# LPDDR4.net
KiCad netlist of a schematic drawn in Altium Designer
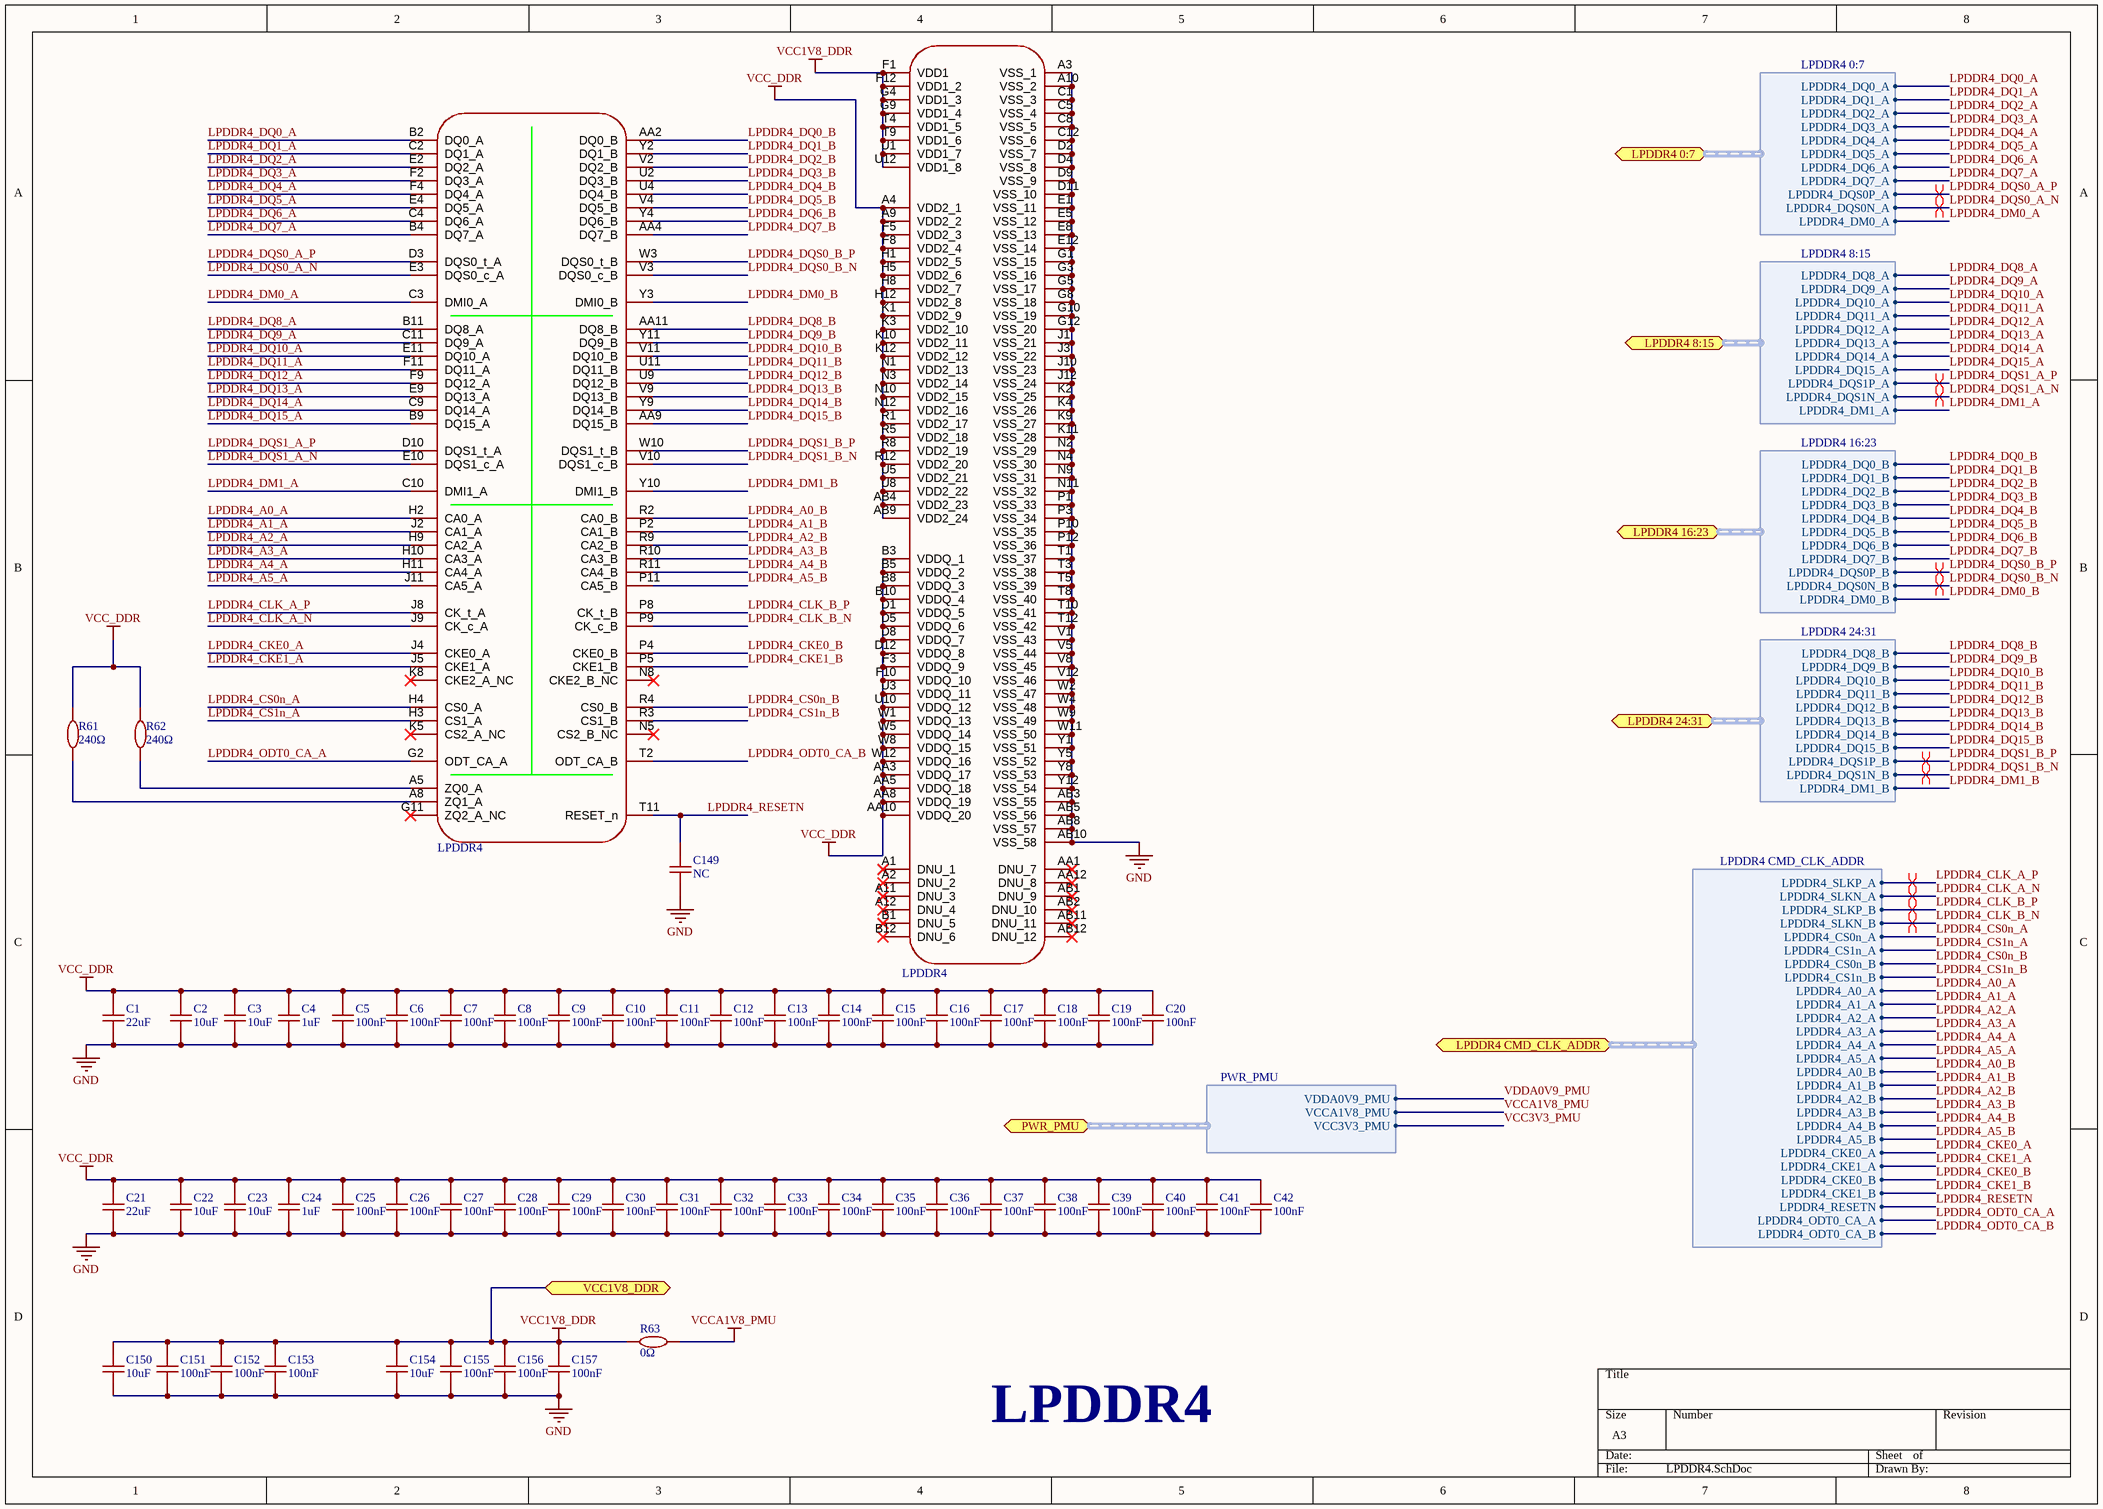
[diagram p0: LPDDR4.SchDoc]

(export (version "E")
  (design (tool "Eeschema 10.0.6"))
  (components
    (comp (ref "C1")
      (value "22uF")
      (footprint "C0603")
      (description "16V 22uF X5R ±20% 0603 Ceramic Capacitors ROHS")
      (libsource (lib "RLC") (part "22uF"))
    )
    (comp (ref "C2")
      (value "10uF")
      (footprint "C0603")
      (description "10V 10uF X5R ±10% 0603 Ceramic Capacitors ROHS")
      (libsource (lib "RLC") (part "10uF"))
    )
    (comp (ref "C3")
      (value "10uF")
      (footprint "C0603")
      (description "10V 10uF X5R ±10% 0603 Ceramic Capacitors ROHS")
      (libsource (lib "RLC") (part "10uF"))
    )
    (comp (ref "C4")
      (value "1uF")
      (footprint "C0402")
      (description "50V 1uF X5R ±10% 0402 Ceramic Capacitors ROHS")
      (libsource (lib "RLC") (part "1uF"))
    )
    (comp (ref "C5")
      (value "100nF")
      (footprint "C0402")
      (description "50V 100nF X7R ±10% 0402 Ceramic Capacitors ROHS")
      (libsource (lib "RLC") (part "100nF"))
    )
    (comp (ref "C6")
      (value "100nF")
      (footprint "C0402")
      (description "50V 100nF X7R ±10% 0402 Ceramic Capacitors ROHS")
      (libsource (lib "RLC") (part "100nF"))
    )
    (comp (ref "C7")
      (value "100nF")
      (footprint "C0402")
      (description "50V 100nF X7R ±10% 0402 Ceramic Capacitors ROHS")
      (libsource (lib "RLC") (part "100nF"))
    )
    (comp (ref "C8")
      (value "100nF")
      (footprint "C0402")
      (description "50V 100nF X7R ±10% 0402 Ceramic Capacitors ROHS")
      (libsource (lib "RLC") (part "100nF"))
    )
    (comp (ref "C9")
      (value "100nF")
      (footprint "C0402")
      (description "50V 100nF X7R ±10% 0402 Ceramic Capacitors ROHS")
      (libsource (lib "RLC") (part "100nF"))
    )
    (comp (ref "C10")
      (value "100nF")
      (footprint "C0402")
      (description "50V 100nF X7R ±10% 0402 Ceramic Capacitors ROHS")
      (libsource (lib "RLC") (part "100nF"))
    )
    (comp (ref "C11")
      (value "100nF")
      (footprint "C0402")
      (description "50V 100nF X7R ±10% 0402 Ceramic Capacitors ROHS")
      (libsource (lib "RLC") (part "100nF"))
    )
    (comp (ref "C12")
      (value "100nF")
      (footprint "C0402")
      (description "50V 100nF X7R ±10% 0402 Ceramic Capacitors ROHS")
      (libsource (lib "RLC") (part "100nF"))
    )
    (comp (ref "C13")
      (value "100nF")
      (footprint "C0402")
      (description "50V 100nF X7R ±10% 0402 Ceramic Capacitors ROHS")
      (libsource (lib "RLC") (part "100nF"))
    )
    (comp (ref "C14")
      (value "100nF")
      (footprint "C0402")
      (description "50V 100nF X7R ±10% 0402 Ceramic Capacitors ROHS")
      (libsource (lib "RLC") (part "100nF"))
    )
    (comp (ref "C15")
      (value "100nF")
      (footprint "C0402")
      (description "50V 100nF X7R ±10% 0402 Ceramic Capacitors ROHS")
      (libsource (lib "RLC") (part "100nF"))
    )
    (comp (ref "C16")
      (value "100nF")
      (footprint "C0402")
      (description "50V 100nF X7R ±10% 0402 Ceramic Capacitors ROHS")
      (libsource (lib "RLC") (part "100nF"))
    )
    (comp (ref "C17")
      (value "100nF")
      (footprint "C0402")
      (description "50V 100nF X7R ±10% 0402 Ceramic Capacitors ROHS")
      (libsource (lib "RLC") (part "100nF"))
    )
    (comp (ref "C18")
      (value "100nF")
      (footprint "C0402")
      (description "50V 100nF X7R ±10% 0402 Ceramic Capacitors ROHS")
      (libsource (lib "RLC") (part "100nF"))
    )
    (comp (ref "C19")
      (value "100nF")
      (footprint "C0402")
      (description "50V 100nF X7R ±10% 0402 Ceramic Capacitors ROHS")
      (libsource (lib "RLC") (part "100nF"))
    )
    (comp (ref "C20")
      (value "100nF")
      (footprint "C0402")
      (description "50V 100nF X7R ±10% 0402 Ceramic Capacitors ROHS")
      (libsource (lib "RLC") (part "100nF"))
    )
    (comp (ref "C21")
      (value "22uF")
      (footprint "C0603")
      (description "16V 22uF X5R ±20% 0603 Ceramic Capacitors ROHS")
      (libsource (lib "RLC") (part "22uF"))
    )
    (comp (ref "C22")
      (value "10uF")
      (footprint "C0603")
      (description "10V 10uF X5R ±10% 0603 Ceramic Capacitors ROHS")
      (libsource (lib "RLC") (part "10uF"))
    )
    (comp (ref "C23")
      (value "10uF")
      (footprint "C0603")
      (description "10V 10uF X5R ±10% 0603 Ceramic Capacitors ROHS")
      (libsource (lib "RLC") (part "10uF"))
    )
    (comp (ref "C24")
      (value "1uF")
      (footprint "C0402")
      (description "50V 1uF X5R ±10% 0402 Ceramic Capacitors ROHS")
      (libsource (lib "RLC") (part "1uF"))
    )
    (comp (ref "C25")
      (value "100nF")
      (footprint "C0402")
      (description "50V 100nF X7R ±10% 0402 Ceramic Capacitors ROHS")
      (libsource (lib "RLC") (part "100nF"))
    )
    (comp (ref "C26")
      (value "100nF")
      (footprint "C0402")
      (description "50V 100nF X7R ±10% 0402 Ceramic Capacitors ROHS")
      (libsource (lib "RLC") (part "100nF"))
    )
    (comp (ref "C27")
      (value "100nF")
      (footprint "C0402")
      (description "50V 100nF X7R ±10% 0402 Ceramic Capacitors ROHS")
      (libsource (lib "RLC") (part "100nF"))
    )
    (comp (ref "C28")
      (value "100nF")
      (footprint "C0402")
      (description "50V 100nF X7R ±10% 0402 Ceramic Capacitors ROHS")
      (libsource (lib "RLC") (part "100nF"))
    )
    (comp (ref "C29")
      (value "100nF")
      (footprint "C0402")
      (description "50V 100nF X7R ±10% 0402 Ceramic Capacitors ROHS")
      (libsource (lib "RLC") (part "100nF"))
    )
    (comp (ref "C30")
      (value "100nF")
      (footprint "C0402")
      (description "50V 100nF X7R ±10% 0402 Ceramic Capacitors ROHS")
      (libsource (lib "RLC") (part "100nF"))
    )
    (comp (ref "C31")
      (value "100nF")
      (footprint "C0402")
      (description "50V 100nF X7R ±10% 0402 Ceramic Capacitors ROHS")
      (libsource (lib "RLC") (part "100nF"))
    )
    (comp (ref "C32")
      (value "100nF")
      (footprint "C0402")
      (description "50V 100nF X7R ±10% 0402 Ceramic Capacitors ROHS")
      (libsource (lib "RLC") (part "100nF"))
    )
    (comp (ref "C33")
      (value "100nF")
      (footprint "C0402")
      (description "50V 100nF X7R ±10% 0402 Ceramic Capacitors ROHS")
      (libsource (lib "RLC") (part "100nF"))
    )
    (comp (ref "C34")
      (value "100nF")
      (footprint "C0402")
      (description "50V 100nF X7R ±10% 0402 Ceramic Capacitors ROHS")
      (libsource (lib "RLC") (part "100nF"))
    )
    (comp (ref "C35")
      (value "100nF")
      (footprint "C0402")
      (description "50V 100nF X7R ±10% 0402 Ceramic Capacitors ROHS")
      (libsource (lib "RLC") (part "100nF"))
    )
    (comp (ref "C36")
      (value "100nF")
      (footprint "C0402")
      (description "50V 100nF X7R ±10% 0402 Ceramic Capacitors ROHS")
      (libsource (lib "RLC") (part "100nF"))
    )
    (comp (ref "C37")
      (value "100nF")
      (footprint "C0402")
      (description "50V 100nF X7R ±10% 0402 Ceramic Capacitors ROHS")
      (libsource (lib "RLC") (part "100nF"))
    )
    (comp (ref "C38")
      (value "100nF")
      (footprint "C0402")
      (description "50V 100nF X7R ±10% 0402 Ceramic Capacitors ROHS")
      (libsource (lib "RLC") (part "100nF"))
    )
    (comp (ref "C39")
      (value "100nF")
      (footprint "C0402")
      (description "50V 100nF X7R ±10% 0402 Ceramic Capacitors ROHS")
      (libsource (lib "RLC") (part "100nF"))
    )
    (comp (ref "C40")
      (value "100nF")
      (footprint "C0402")
      (description "50V 100nF X7R ±10% 0402 Ceramic Capacitors ROHS")
      (libsource (lib "RLC") (part "100nF"))
    )
    (comp (ref "C41")
      (value "100nF")
      (footprint "C0402")
      (description "50V 100nF X7R ±10% 0402 Ceramic Capacitors ROHS")
      (libsource (lib "RLC") (part "100nF"))
    )
    (comp (ref "C42")
      (value "100nF")
      (footprint "C0402")
      (description "50V 100nF X7R ±10% 0402 Ceramic Capacitors ROHS")
      (libsource (lib "RLC") (part "100nF"))
    )
    (comp (ref "C149")
      (value "NC")
      (footprint "C0402")
      (description "50V 10nF X7R ±10% 0402 Ceramic Capacitors ROHS")
      (libsource (lib "RLC") (part "10nF"))
    )
    (comp (ref "C150")
      (value "10uF")
      (footprint "C0603")
      (description "10V 10uF X5R ±10% 0603 Ceramic Capacitors ROHS")
      (libsource (lib "RLC") (part "10uF"))
    )
    (comp (ref "C151")
      (value "100nF")
      (footprint "C0402")
      (description "50V 100nF X7R ±10% 0402 Ceramic Capacitors ROHS")
      (libsource (lib "RLC") (part "100nF"))
    )
    (comp (ref "C152")
      (value "100nF")
      (footprint "C0402")
      (description "50V 100nF X7R ±10% 0402 Ceramic Capacitors ROHS")
      (libsource (lib "RLC") (part "100nF"))
    )
    (comp (ref "C153")
      (value "100nF")
      (footprint "C0402")
      (description "50V 100nF X7R ±10% 0402 Ceramic Capacitors ROHS")
      (libsource (lib "RLC") (part "100nF"))
    )
    (comp (ref "C154")
      (value "10uF")
      (footprint "C0603")
      (description "10V 10uF X5R ±10% 0603 Ceramic Capacitors ROHS")
      (libsource (lib "RLC") (part "10uF"))
    )
    (comp (ref "C155")
      (value "100nF")
      (footprint "C0402")
      (description "50V 100nF X7R ±10% 0402 Ceramic Capacitors ROHS")
      (libsource (lib "RLC") (part "100nF"))
    )
    (comp (ref "C156")
      (value "100nF")
      (footprint "C0402")
      (description "50V 100nF X7R ±10% 0402 Ceramic Capacitors ROHS")
      (libsource (lib "RLC") (part "100nF"))
    )
    (comp (ref "C157")
      (value "100nF")
      (footprint "C0402")
      (description "50V 100nF X7R ±10% 0402 Ceramic Capacitors ROHS")
      (libsource (lib "RLC") (part "100nF"))
    )
    (comp (ref "R61")
      (value "240Ω")
      (footprint "R0402")
      (description "240Ω 62.5mW 50V ±100ppm/℃ Thick Film Resistor ±1% 0402 Chip Resistor - Surface Mount ROHS")
      (libsource (lib "RLC") (part "240Ω"))
    )
    (comp (ref "R62")
      (value "240Ω")
      (footprint "R0402")
      (description "240Ω 62.5mW 50V ±100ppm/℃ Thick Film Resistor ±1% 0402 Chip Resistor - Surface Mount ROHS")
      (libsource (lib "RLC") (part "240Ω"))
    )
    (comp (ref "R63")
      (value "0Ω")
      (footprint "R0402")
      (description "0Ω 62.5mW 50V Thick Film Resistor ±1% 0402 Chip Resistor - Surface Mount ROHS")
      (libsource (lib "RLC") (part "0Ω"))
    )
    (comp (ref "U1")
      (value "LPDDR4")
      (footprint "FBGA-200_L15.0-W10.0-BL_H9HCNNNBKUMLXR")
      (description "LPDDR4 - SDRAM是一种高速同步DRAM器件，内部配置有1个或2个通道。单通道由8个存储体组成，每通道密度为1 Gb至16 Gb。双通道由8个存储体组成，每通道密度为2 Gb至32 Gb")
      (libsource (lib "IC") (part "LPDDR4"))
    )
  )
  (nets
    (net (code "8") (name "/LPDDR4_A0_A") (class "Default")
      (node (ref "U1") (pin "H2") (pinfunction "CA0_A_H2") (pintype "passive"))
    )
    (net (code "9") (name "/LPDDR4_A0_B") (class "Default")
      (node (ref "U1") (pin "R2") (pinfunction "CA0_B_R2") (pintype "passive"))
    )
    (net (code "10") (name "/LPDDR4_A1_A") (class "Default")
      (node (ref "U1") (pin "J2") (pinfunction "CA1_A_J2") (pintype "passive"))
    )
    (net (code "11") (name "/LPDDR4_A1_B") (class "Default")
      (node (ref "U1") (pin "P2") (pinfunction "CA1_B_P2") (pintype "passive"))
    )
    (net (code "12") (name "/LPDDR4_A2_A") (class "Default")
      (node (ref "U1") (pin "H9") (pinfunction "CA2_A_H9") (pintype "passive"))
    )
    (net (code "13") (name "/LPDDR4_A2_B") (class "Default")
      (node (ref "U1") (pin "R9") (pinfunction "CA2_B_R9") (pintype "passive"))
    )
    (net (code "14") (name "/LPDDR4_A3_A") (class "Default")
      (node (ref "U1") (pin "H10") (pinfunction "CA3_A_H10") (pintype "passive"))
    )
    (net (code "15") (name "/LPDDR4_A3_B") (class "Default")
      (node (ref "U1") (pin "R10") (pinfunction "CA3_B_R10") (pintype "passive"))
    )
    (net (code "16") (name "/LPDDR4_A4_A") (class "Default")
      (node (ref "U1") (pin "H11") (pinfunction "CA4_A_H11") (pintype "passive"))
    )
    (net (code "17") (name "/LPDDR4_A4_B") (class "Default")
      (node (ref "U1") (pin "R11") (pinfunction "CA4_B_R11") (pintype "passive"))
    )
    (net (code "18") (name "/LPDDR4_A5_A") (class "Default")
      (node (ref "U1") (pin "J11") (pinfunction "CA5_A_J11") (pintype "passive"))
    )
    (net (code "19") (name "/LPDDR4_A5_B") (class "Default")
      (node (ref "U1") (pin "P11") (pinfunction "CA5_B_P11") (pintype "passive"))
    )
    (net (code "20") (name "/LPDDR4_CKE0_A") (class "Default")
      (node (ref "U1") (pin "J4") (pinfunction "CKE0_A_J4") (pintype "passive"))
    )
    (net (code "21") (name "/LPDDR4_CKE0_B") (class "Default")
      (node (ref "U1") (pin "P4") (pinfunction "CKE0_B_P4") (pintype "passive"))
    )
    (net (code "22") (name "/LPDDR4_CKE1_A") (class "Default")
      (node (ref "U1") (pin "J5") (pinfunction "CKE1_A_J5") (pintype "passive"))
    )
    (net (code "23") (name "/LPDDR4_CKE1_B") (class "Default")
      (node (ref "U1") (pin "P5") (pinfunction "CKE1_B_P5") (pintype "passive"))
    )
    (net (code "24") (name "/LPDDR4_CLK_A_N") (class "Default")
      (node (ref "U1") (pin "J9") (pinfunction "CK_c_A_J9") (pintype "passive"))
    )
    (net (code "25") (name "/LPDDR4_CLK_A_P") (class "Default")
      (node (ref "U1") (pin "J8") (pinfunction "CK_t_A_J8") (pintype "passive"))
    )
    (net (code "26") (name "/LPDDR4_CLK_B_N") (class "Default")
      (node (ref "U1") (pin "P9") (pinfunction "CK_c_B_P9") (pintype "passive"))
    )
    (net (code "27") (name "/LPDDR4_CLK_B_P") (class "Default")
      (node (ref "U1") (pin "P8") (pinfunction "CK_t_B_P8") (pintype "passive"))
    )
    (net (code "28") (name "/LPDDR4_CS0n_A") (class "Default")
      (node (ref "U1") (pin "H4") (pinfunction "CS0_A_H4") (pintype "passive"))
    )
    (net (code "29") (name "/LPDDR4_CS0n_B") (class "Default")
      (node (ref "U1") (pin "R4") (pinfunction "CS0_B_R4") (pintype "passive"))
    )
    (net (code "30") (name "/LPDDR4_CS1n_A") (class "Default")
      (node (ref "U1") (pin "H3") (pinfunction "CS1_A_H3") (pintype "passive"))
    )
    (net (code "31") (name "/LPDDR4_CS1n_B") (class "Default")
      (node (ref "U1") (pin "R3") (pinfunction "CS1_B_R3") (pintype "passive"))
    )
    (net (code "32") (name "/LPDDR4_DM0_A") (class "Default")
      (node (ref "U1") (pin "C3") (pinfunction "DMI0_A_C3") (pintype "passive"))
    )
    (net (code "33") (name "/LPDDR4_DM0_B") (class "Default")
      (node (ref "U1") (pin "Y3") (pinfunction "DMI0_B_Y3") (pintype "passive"))
    )
    (net (code "34") (name "/LPDDR4_DM1_A") (class "Default")
      (node (ref "U1") (pin "C10") (pinfunction "DMI1_A_C10") (pintype "passive"))
    )
    (net (code "35") (name "/LPDDR4_DM1_B") (class "Default")
      (node (ref "U1") (pin "Y10") (pinfunction "DMI1_B_Y10") (pintype "passive"))
    )
    (net (code "36") (name "/LPDDR4_DQ0_A") (class "Default")
      (node (ref "U1") (pin "B2") (pinfunction "DQ0_A_B2") (pintype "passive"))
    )
    (net (code "37") (name "/LPDDR4_DQ0_B") (class "Default")
      (node (ref "U1") (pin "AA2") (pinfunction "DQ0_B_AA2") (pintype "passive"))
    )
    (net (code "38") (name "/LPDDR4_DQ1_A") (class "Default")
      (node (ref "U1") (pin "C2") (pinfunction "DQ1_A_C2") (pintype "passive"))
    )
    (net (code "39") (name "/LPDDR4_DQ1_B") (class "Default")
      (node (ref "U1") (pin "Y2") (pinfunction "DQ1_B_Y2") (pintype "passive"))
    )
    (net (code "40") (name "/LPDDR4_DQ2_A") (class "Default")
      (node (ref "U1") (pin "E2") (pinfunction "DQ2_A_E2") (pintype "passive"))
    )
    (net (code "41") (name "/LPDDR4_DQ2_B") (class "Default")
      (node (ref "U1") (pin "V2") (pinfunction "DQ2_B_V2") (pintype "passive"))
    )
    (net (code "42") (name "/LPDDR4_DQ3_A") (class "Default")
      (node (ref "U1") (pin "F2") (pinfunction "DQ3_A_F2") (pintype "passive"))
    )
    (net (code "43") (name "/LPDDR4_DQ3_B") (class "Default")
      (node (ref "U1") (pin "U2") (pinfunction "DQ3_B_U2") (pintype "passive"))
    )
    (net (code "44") (name "/LPDDR4_DQ4_A") (class "Default")
      (node (ref "U1") (pin "F4") (pinfunction "DQ4_A_F4") (pintype "passive"))
    )
    (net (code "45") (name "/LPDDR4_DQ4_B") (class "Default")
      (node (ref "U1") (pin "U4") (pinfunction "DQ4_B_U4") (pintype "passive"))
    )
    (net (code "46") (name "/LPDDR4_DQ5_A") (class "Default")
      (node (ref "U1") (pin "E4") (pinfunction "DQ5_A_E4") (pintype "passive"))
    )
    (net (code "47") (name "/LPDDR4_DQ5_B") (class "Default")
      (node (ref "U1") (pin "V4") (pinfunction "DQ5_B_V4") (pintype "passive"))
    )
    (net (code "48") (name "/LPDDR4_DQ6_A") (class "Default")
      (node (ref "U1") (pin "C4") (pinfunction "DQ6_A_C4") (pintype "passive"))
    )
    (net (code "49") (name "/LPDDR4_DQ6_B") (class "Default")
      (node (ref "U1") (pin "Y4") (pinfunction "DQ6_B_Y4") (pintype "passive"))
    )
    (net (code "50") (name "/LPDDR4_DQ7_A") (class "Default")
      (node (ref "U1") (pin "B4") (pinfunction "DQ7_A_B4") (pintype "passive"))
    )
    (net (code "51") (name "/LPDDR4_DQ7_B") (class "Default")
      (node (ref "U1") (pin "AA4") (pinfunction "DQ7_B_AA4") (pintype "passive"))
    )
    (net (code "52") (name "/LPDDR4_DQ8_A") (class "Default")
      (node (ref "U1") (pin "B11") (pinfunction "DQ8_A_B11") (pintype "passive"))
    )
    (net (code "53") (name "/LPDDR4_DQ8_B") (class "Default")
      (node (ref "U1") (pin "AA11") (pinfunction "DQ8_B_AA11") (pintype "passive"))
    )
    (net (code "54") (name "/LPDDR4_DQ9_A") (class "Default")
      (node (ref "U1") (pin "C11") (pinfunction "DQ9_A_C11") (pintype "passive"))
    )
    (net (code "55") (name "/LPDDR4_DQ9_B") (class "Default")
      (node (ref "U1") (pin "Y11") (pinfunction "DQ9_B_Y11") (pintype "passive"))
    )
    (net (code "56") (name "/LPDDR4_DQ10_A") (class "Default")
      (node (ref "U1") (pin "E11") (pinfunction "DQ10_A_E11") (pintype "passive"))
    )
    (net (code "57") (name "/LPDDR4_DQ10_B") (class "Default")
      (node (ref "U1") (pin "V11") (pinfunction "DQ10_B_V11") (pintype "passive"))
    )
    (net (code "58") (name "/LPDDR4_DQ11_A") (class "Default")
      (node (ref "U1") (pin "F11") (pinfunction "DQ11_A_F11") (pintype "passive"))
    )
    (net (code "59") (name "/LPDDR4_DQ11_B") (class "Default")
      (node (ref "U1") (pin "U11") (pinfunction "DQ11_B_U11") (pintype "passive"))
    )
    (net (code "60") (name "/LPDDR4_DQ12_A") (class "Default")
      (node (ref "U1") (pin "F9") (pinfunction "DQ12_A_F9") (pintype "passive"))
    )
    (net (code "61") (name "/LPDDR4_DQ12_B") (class "Default")
      (node (ref "U1") (pin "U9") (pinfunction "DQ12_B_U9") (pintype "passive"))
    )
    (net (code "62") (name "/LPDDR4_DQ13_A") (class "Default")
      (node (ref "U1") (pin "E9") (pinfunction "DQ13_A_E9") (pintype "passive"))
    )
    (net (code "63") (name "/LPDDR4_DQ13_B") (class "Default")
      (node (ref "U1") (pin "V9") (pinfunction "DQ13_B_V9") (pintype "passive"))
    )
    (net (code "64") (name "/LPDDR4_DQ14_A") (class "Default")
      (node (ref "U1") (pin "C9") (pinfunction "DQ14_A_C9") (pintype "passive"))
    )
    (net (code "65") (name "/LPDDR4_DQ14_B") (class "Default")
      (node (ref "U1") (pin "Y9") (pinfunction "DQ14_B_Y9") (pintype "passive"))
    )
    (net (code "66") (name "/LPDDR4_DQ15_A") (class "Default")
      (node (ref "U1") (pin "B9") (pinfunction "DQ15_A_B9") (pintype "passive"))
    )
    (net (code "67") (name "/LPDDR4_DQ15_B") (class "Default")
      (node (ref "U1") (pin "AA9") (pinfunction "DQ15_B_AA9") (pintype "passive"))
    )
    (net (code "68") (name "/LPDDR4_DQS0_A_N") (class "Default")
      (node (ref "U1") (pin "E3") (pinfunction "DQS0_c_A_E3") (pintype "passive"))
    )
    (net (code "69") (name "/LPDDR4_DQS0_A_P") (class "Default")
      (node (ref "U1") (pin "D3") (pinfunction "DQS0_t_A_D3") (pintype "passive"))
    )
    (net (code "70") (name "/LPDDR4_DQS0_B_N") (class "Default")
      (node (ref "U1") (pin "V3") (pinfunction "DQS0_c_B_V3") (pintype "passive"))
    )
    (net (code "71") (name "/LPDDR4_DQS0_B_P") (class "Default")
      (node (ref "U1") (pin "W3") (pinfunction "DQS0_t_B_W3") (pintype "passive"))
    )
    (net (code "72") (name "/LPDDR4_DQS1_A_N") (class "Default")
      (node (ref "U1") (pin "E10") (pinfunction "DQS1_c_A_E10") (pintype "passive"))
    )
    (net (code "73") (name "/LPDDR4_DQS1_A_P") (class "Default")
      (node (ref "U1") (pin "D10") (pinfunction "DQS1_t_A_D10") (pintype "passive"))
    )
    (net (code "74") (name "/LPDDR4_DQS1_B_N") (class "Default")
      (node (ref "U1") (pin "V10") (pinfunction "DQS1_c_B_V10") (pintype "passive"))
    )
    (net (code "75") (name "/LPDDR4_DQS1_B_P") (class "Default")
      (node (ref "U1") (pin "W10") (pinfunction "DQS1_t_B_W10") (pintype "passive"))
    )
    (net (code "76") (name "/LPDDR4_ODT0_CA_A") (class "Default")
      (node (ref "U1") (pin "G2") (pinfunction "ODT_CA_A_G2") (pintype "passive"))
    )
    (net (code "77") (name "/LPDDR4_ODT0_CA_B") (class "Default")
      (node (ref "U1") (pin "T2") (pinfunction "ODT_CA_B_T2") (pintype "passive"))
    )
    (net (code "78") (name "/LPDDR4_RESETN") (class "Default")
      (node (ref "C149") (pin "2") (pinfunction "2_2") (pintype "passive"))
      (node (ref "U1") (pin "T11") (pinfunction "RESET_n_T11") (pintype "passive"))
    )
    (net (code "87") (name "GND") (class "Default")
      (node (ref "C1") (pin "1") (pinfunction "1_1") (pintype "passive"))
      (node (ref "C10") (pin "1") (pinfunction "1_1") (pintype "passive"))
      (node (ref "C11") (pin "1") (pinfunction "1_1") (pintype "passive"))
      (node (ref "C12") (pin "1") (pinfunction "1_1") (pintype "passive"))
      (node (ref "C13") (pin "1") (pinfunction "1_1") (pintype "passive"))
      (node (ref "C14") (pin "1") (pinfunction "1_1") (pintype "passive"))
      (node (ref "C149") (pin "1") (pinfunction "1_1") (pintype "passive"))
      (node (ref "C15") (pin "1") (pinfunction "1_1") (pintype "passive"))
      (node (ref "C150") (pin "1") (pinfunction "1_1") (pintype "passive"))
      (node (ref "C151") (pin "1") (pinfunction "1_1") (pintype "passive"))
      (node (ref "C152") (pin "1") (pinfunction "1_1") (pintype "passive"))
      (node (ref "C153") (pin "1") (pinfunction "1_1") (pintype "passive"))
      (node (ref "C154") (pin "1") (pinfunction "1_1") (pintype "passive"))
      (node (ref "C155") (pin "1") (pinfunction "1_1") (pintype "passive"))
      (node (ref "C156") (pin "1") (pinfunction "1_1") (pintype "passive"))
      (node (ref "C157") (pin "1") (pinfunction "1_1") (pintype "passive"))
      (node (ref "C16") (pin "1") (pinfunction "1_1") (pintype "passive"))
      (node (ref "C17") (pin "1") (pinfunction "1_1") (pintype "passive"))
      (node (ref "C18") (pin "1") (pinfunction "1_1") (pintype "passive"))
      (node (ref "C19") (pin "1") (pinfunction "1_1") (pintype "passive"))
      (node (ref "C2") (pin "1") (pinfunction "1_1") (pintype "passive"))
      (node (ref "C20") (pin "1") (pinfunction "1_1") (pintype "passive"))
      (node (ref "C21") (pin "1") (pinfunction "1_1") (pintype "passive"))
      (node (ref "C22") (pin "1") (pinfunction "1_1") (pintype "passive"))
      (node (ref "C23") (pin "1") (pinfunction "1_1") (pintype "passive"))
      (node (ref "C24") (pin "1") (pinfunction "1_1") (pintype "passive"))
      (node (ref "C25") (pin "1") (pinfunction "1_1") (pintype "passive"))
      (node (ref "C26") (pin "1") (pinfunction "1_1") (pintype "passive"))
      (node (ref "C27") (pin "1") (pinfunction "1_1") (pintype "passive"))
      (node (ref "C28") (pin "1") (pinfunction "1_1") (pintype "passive"))
      (node (ref "C29") (pin "1") (pinfunction "1_1") (pintype "passive"))
      (node (ref "C3") (pin "1") (pinfunction "1_1") (pintype "passive"))
      (node (ref "C30") (pin "1") (pinfunction "1_1") (pintype "passive"))
      (node (ref "C31") (pin "1") (pinfunction "1_1") (pintype "passive"))
      (node (ref "C32") (pin "1") (pinfunction "1_1") (pintype "passive"))
      (node (ref "C33") (pin "1") (pinfunction "1_1") (pintype "passive"))
      (node (ref "C34") (pin "1") (pinfunction "1_1") (pintype "passive"))
      (node (ref "C35") (pin "1") (pinfunction "1_1") (pintype "passive"))
      (node (ref "C36") (pin "1") (pinfunction "1_1") (pintype "passive"))
      (node (ref "C37") (pin "1") (pinfunction "1_1") (pintype "passive"))
      (node (ref "C38") (pin "1") (pinfunction "1_1") (pintype "passive"))
      (node (ref "C39") (pin "1") (pinfunction "1_1") (pintype "passive"))
      (node (ref "C4") (pin "1") (pinfunction "1_1") (pintype "passive"))
      (node (ref "C40") (pin "1") (pinfunction "1_1") (pintype "passive"))
      (node (ref "C41") (pin "1") (pinfunction "1_1") (pintype "passive"))
      (node (ref "C42") (pin "1") (pinfunction "1_1") (pintype "passive"))
      (node (ref "C5") (pin "1") (pinfunction "1_1") (pintype "passive"))
      (node (ref "C6") (pin "1") (pinfunction "1_1") (pintype "passive"))
      (node (ref "C7") (pin "1") (pinfunction "1_1") (pintype "passive"))
      (node (ref "C8") (pin "1") (pinfunction "1_1") (pintype "passive"))
      (node (ref "C9") (pin "1") (pinfunction "1_1") (pintype "passive"))
      (node (ref "U1") (pin "A10") (pinfunction "VSS_2_A10") (pintype "passive"))
      (node (ref "U1") (pin "A3") (pinfunction "VSS_1_A3") (pintype "passive"))
      (node (ref "U1") (pin "AB10") (pinfunction "VSS_58_AB10") (pintype "passive"))
      (node (ref "U1") (pin "AB3") (pinfunction "VSS_55_AB3") (pintype "passive"))
      (node (ref "U1") (pin "AB5") (pinfunction "VSS_56_AB5") (pintype "passive"))
      (node (ref "U1") (pin "AB8") (pinfunction "VSS_57_AB8") (pintype "passive"))
      (node (ref "U1") (pin "C1") (pinfunction "VSS_3_C1") (pintype "passive"))
      (node (ref "U1") (pin "C12") (pinfunction "VSS_6_C12") (pintype "passive"))
      (node (ref "U1") (pin "C5") (pinfunction "VSS_4_C5") (pintype "passive"))
      (node (ref "U1") (pin "C8") (pinfunction "VSS_5_C8") (pintype "passive"))
      (node (ref "U1") (pin "D11") (pinfunction "VSS_10_D11") (pintype "passive"))
      (node (ref "U1") (pin "D2") (pinfunction "VSS_7_D2") (pintype "passive"))
      (node (ref "U1") (pin "D4") (pinfunction "VSS_8_D4") (pintype "passive"))
      (node (ref "U1") (pin "D9") (pinfunction "VSS_9_D9") (pintype "passive"))
      (node (ref "U1") (pin "E1") (pinfunction "VSS_11_E1") (pintype "passive"))
      (node (ref "U1") (pin "E12") (pinfunction "VSS_14_E12") (pintype "passive"))
      (node (ref "U1") (pin "E5") (pinfunction "VSS_12_E5") (pintype "passive"))
      (node (ref "U1") (pin "E8") (pinfunction "VSS_13_E8") (pintype "passive"))
      (node (ref "U1") (pin "G1") (pinfunction "VSS_15_G1") (pintype "passive"))
      (node (ref "U1") (pin "G10") (pinfunction "VSS_19_G10") (pintype "passive"))
      (node (ref "U1") (pin "G12") (pinfunction "VSS_20_G12") (pintype "passive"))
      (node (ref "U1") (pin "G3") (pinfunction "VSS_16_G3") (pintype "passive"))
      (node (ref "U1") (pin "G5") (pinfunction "VSS_17_G5") (pintype "passive"))
      (node (ref "U1") (pin "G8") (pinfunction "VSS_18_G8") (pintype "passive"))
      (node (ref "U1") (pin "J1") (pinfunction "VSS_21_J1") (pintype "passive"))
      (node (ref "U1") (pin "J10") (pinfunction "VSS_23_J10") (pintype "passive"))
      (node (ref "U1") (pin "J12") (pinfunction "VSS_24_J12") (pintype "passive"))
      (node (ref "U1") (pin "J3") (pinfunction "VSS_22_J3") (pintype "passive"))
      (node (ref "U1") (pin "K11") (pinfunction "VSS_28_K11") (pintype "passive"))
      (node (ref "U1") (pin "K2") (pinfunction "VSS_25_K2") (pintype "passive"))
      (node (ref "U1") (pin "K4") (pinfunction "VSS_26_K4") (pintype "passive"))
      (node (ref "U1") (pin "K9") (pinfunction "VSS_27_K9") (pintype "passive"))
      (node (ref "U1") (pin "N11") (pinfunction "VSS_32_N11") (pintype "passive"))
      (node (ref "U1") (pin "N2") (pinfunction "VSS_29_N2") (pintype "passive"))
      (node (ref "U1") (pin "N4") (pinfunction "VSS_30_N4") (pintype "passive"))
      (node (ref "U1") (pin "N9") (pinfunction "VSS_31_N9") (pintype "passive"))
      (node (ref "U1") (pin "P1") (pinfunction "VSS_33_P1") (pintype "passive"))
      (node (ref "U1") (pin "P10") (pinfunction "VSS_35_P10") (pintype "passive"))
      (node (ref "U1") (pin "P12") (pinfunction "VSS_36_P12") (pintype "passive"))
      (node (ref "U1") (pin "P3") (pinfunction "VSS_34_P3") (pintype "passive"))
      (node (ref "U1") (pin "T1") (pinfunction "VSS_37_T1") (pintype "passive"))
      (node (ref "U1") (pin "T10") (pinfunction "VSS_41_T10") (pintype "passive"))
      (node (ref "U1") (pin "T12") (pinfunction "VSS_42_T12") (pintype "passive"))
      (node (ref "U1") (pin "T3") (pinfunction "VSS_38_T3") (pintype "passive"))
      (node (ref "U1") (pin "T5") (pinfunction "VSS_39_T5") (pintype "passive"))
      (node (ref "U1") (pin "T8") (pinfunction "VSS_40_T8") (pintype "passive"))
      (node (ref "U1") (pin "V1") (pinfunction "VSS_43_V1") (pintype "passive"))
      (node (ref "U1") (pin "V12") (pinfunction "VSS_46_V12") (pintype "passive"))
      (node (ref "U1") (pin "V5") (pinfunction "VSS_44_V5") (pintype "passive"))
      (node (ref "U1") (pin "V8") (pinfunction "VSS_45_V8") (pintype "passive"))
      (node (ref "U1") (pin "W11") (pinfunction "VSS_50_W11") (pintype "passive"))
      (node (ref "U1") (pin "W2") (pinfunction "VSS_47_W2") (pintype "passive"))
      (node (ref "U1") (pin "W4") (pinfunction "VSS_48_W4") (pintype "passive"))
      (node (ref "U1") (pin "W9") (pinfunction "VSS_49_W9") (pintype "passive"))
      (node (ref "U1") (pin "Y1") (pinfunction "VSS_51_Y1") (pintype "passive"))
      (node (ref "U1") (pin "Y12") (pinfunction "VSS_54_Y12") (pintype "passive"))
      (node (ref "U1") (pin "Y5") (pinfunction "VSS_52_Y5") (pintype "passive"))
      (node (ref "U1") (pin "Y8") (pinfunction "VSS_53_Y8") (pintype "passive"))
    )
    (net (code "88") (name "Net-(U1A-ZQ0_A)") (class "Default")
      (node (ref "R62") (pin "1") (pinfunction "1_1") (pintype "passive"))
      (node (ref "U1") (pin "A5") (pinfunction "ZQ0_A_A5") (pintype "passive"))
    )
    (net (code "89") (name "Net-(U1A-ZQ1_A)") (class "Default")
      (node (ref "R61") (pin "1") (pinfunction "1_1") (pintype "passive"))
      (node (ref "U1") (pin "A8") (pinfunction "ZQ1_A_A8") (pintype "passive"))
    )
    (net (code "90") (name "VCC1V8_DDR") (class "Default")
      (node (ref "C150") (pin "2") (pinfunction "2_2") (pintype "passive"))
      (node (ref "C151") (pin "2") (pinfunction "2_2") (pintype "passive"))
      (node (ref "C152") (pin "2") (pinfunction "2_2") (pintype "passive"))
      (node (ref "C153") (pin "2") (pinfunction "2_2") (pintype "passive"))
      (node (ref "C154") (pin "2") (pinfunction "2_2") (pintype "passive"))
      (node (ref "C155") (pin "2") (pinfunction "2_2") (pintype "passive"))
      (node (ref "C156") (pin "2") (pinfunction "2_2") (pintype "passive"))
      (node (ref "C157") (pin "2") (pinfunction "2_2") (pintype "passive"))
      (node (ref "R63") (pin "1") (pinfunction "1_1") (pintype "passive"))
      (node (ref "U1") (pin "F1") (pinfunction "VDD1_F1") (pintype "passive"))
      (node (ref "U1") (pin "F12") (pinfunction "VDD1_2_F12") (pintype "passive"))
      (node (ref "U1") (pin "G4") (pinfunction "VDD1_3_G4") (pintype "passive"))
      (node (ref "U1") (pin "G9") (pinfunction "VDD1_4_G9") (pintype "passive"))
      (node (ref "U1") (pin "T4") (pinfunction "VDD1_5_T4") (pintype "passive"))
      (node (ref "U1") (pin "T9") (pinfunction "VDD1_6_T9") (pintype "passive"))
      (node (ref "U1") (pin "U1") (pinfunction "VDD1_7_U1") (pintype "passive"))
      (node (ref "U1") (pin "U12") (pinfunction "VDD1_8_U12") (pintype "passive"))
    )
    (net (code "91") (name "VCCA1V8_PMU") (class "Default")
      (node (ref "R63") (pin "2") (pinfunction "2_2") (pintype "passive"))
    )
    (net (code "92") (name "VCC_DDR") (class "Default")
      (node (ref "C1") (pin "2") (pinfunction "2_2") (pintype "passive"))
      (node (ref "C10") (pin "2") (pinfunction "2_2") (pintype "passive"))
      (node (ref "C11") (pin "2") (pinfunction "2_2") (pintype "passive"))
      (node (ref "C12") (pin "2") (pinfunction "2_2") (pintype "passive"))
      (node (ref "C13") (pin "2") (pinfunction "2_2") (pintype "passive"))
      (node (ref "C14") (pin "2") (pinfunction "2_2") (pintype "passive"))
      (node (ref "C15") (pin "2") (pinfunction "2_2") (pintype "passive"))
      (node (ref "C16") (pin "2") (pinfunction "2_2") (pintype "passive"))
      (node (ref "C17") (pin "2") (pinfunction "2_2") (pintype "passive"))
      (node (ref "C18") (pin "2") (pinfunction "2_2") (pintype "passive"))
      (node (ref "C19") (pin "2") (pinfunction "2_2") (pintype "passive"))
      (node (ref "C2") (pin "2") (pinfunction "2_2") (pintype "passive"))
      (node (ref "C20") (pin "2") (pinfunction "2_2") (pintype "passive"))
      (node (ref "C21") (pin "2") (pinfunction "2_2") (pintype "passive"))
      (node (ref "C22") (pin "2") (pinfunction "2_2") (pintype "passive"))
      (node (ref "C23") (pin "2") (pinfunction "2_2") (pintype "passive"))
      (node (ref "C24") (pin "2") (pinfunction "2_2") (pintype "passive"))
      (node (ref "C25") (pin "2") (pinfunction "2_2") (pintype "passive"))
      (node (ref "C26") (pin "2") (pinfunction "2_2") (pintype "passive"))
      (node (ref "C27") (pin "2") (pinfunction "2_2") (pintype "passive"))
      (node (ref "C28") (pin "2") (pinfunction "2_2") (pintype "passive"))
      (node (ref "C29") (pin "2") (pinfunction "2_2") (pintype "passive"))
      (node (ref "C3") (pin "2") (pinfunction "2_2") (pintype "passive"))
      (node (ref "C30") (pin "2") (pinfunction "2_2") (pintype "passive"))
      (node (ref "C31") (pin "2") (pinfunction "2_2") (pintype "passive"))
      (node (ref "C32") (pin "2") (pinfunction "2_2") (pintype "passive"))
      (node (ref "C33") (pin "2") (pinfunction "2_2") (pintype "passive"))
      (node (ref "C34") (pin "2") (pinfunction "2_2") (pintype "passive"))
      (node (ref "C35") (pin "2") (pinfunction "2_2") (pintype "passive"))
      (node (ref "C36") (pin "2") (pinfunction "2_2") (pintype "passive"))
      (node (ref "C37") (pin "2") (pinfunction "2_2") (pintype "passive"))
      (node (ref "C38") (pin "2") (pinfunction "2_2") (pintype "passive"))
      (node (ref "C39") (pin "2") (pinfunction "2_2") (pintype "passive"))
      (node (ref "C4") (pin "2") (pinfunction "2_2") (pintype "passive"))
      (node (ref "C40") (pin "2") (pinfunction "2_2") (pintype "passive"))
      (node (ref "C41") (pin "2") (pinfunction "2_2") (pintype "passive"))
      (node (ref "C42") (pin "2") (pinfunction "2_2") (pintype "passive"))
      (node (ref "C5") (pin "2") (pinfunction "2_2") (pintype "passive"))
      (node (ref "C6") (pin "2") (pinfunction "2_2") (pintype "passive"))
      (node (ref "C7") (pin "2") (pinfunction "2_2") (pintype "passive"))
      (node (ref "C8") (pin "2") (pinfunction "2_2") (pintype "passive"))
      (node (ref "C9") (pin "2") (pinfunction "2_2") (pintype "passive"))
      (node (ref "R61") (pin "2") (pinfunction "2_2") (pintype "passive"))
      (node (ref "R62") (pin "2") (pinfunction "2_2") (pintype "passive"))
      (node (ref "U1") (pin "A4") (pinfunction "VDD2_1_A4") (pintype "passive"))
      (node (ref "U1") (pin "A9") (pinfunction "VDD2_2_A9") (pintype "passive"))
      (node (ref "U1") (pin "AA10") (pinfunction "VDDQ_20_AA10") (pintype "passive"))
      (node (ref "U1") (pin "AA3") (pinfunction "VDDQ_17_AA3") (pintype "passive"))
      (node (ref "U1") (pin "AA5") (pinfunction "VDDQ_18_AA5") (pintype "passive"))
      (node (ref "U1") (pin "AA8") (pinfunction "VDDQ_19_AA8") (pintype "passive"))
      (node (ref "U1") (pin "AB4") (pinfunction "VDD2_23_AB4") (pintype "passive"))
      (node (ref "U1") (pin "AB9") (pinfunction "VDD2_24_AB9") (pintype "passive"))
      (node (ref "U1") (pin "B10") (pinfunction "VDDQ_4_B10") (pintype "passive"))
      (node (ref "U1") (pin "B3") (pinfunction "VDDQ_1_B3") (pintype "passive"))
      (node (ref "U1") (pin "B5") (pinfunction "VDDQ_2_B5") (pintype "passive"))
      (node (ref "U1") (pin "B8") (pinfunction "VDDQ_3_B8") (pintype "passive"))
      (node (ref "U1") (pin "D1") (pinfunction "VDDQ_5_D1") (pintype "passive"))
      (node (ref "U1") (pin "D12") (pinfunction "VDDQ_8_D12") (pintype "passive"))
      (node (ref "U1") (pin "D5") (pinfunction "VDDQ_6_D5") (pintype "passive"))
      (node (ref "U1") (pin "D8") (pinfunction "VDDQ_7_D8") (pintype "passive"))
      (node (ref "U1") (pin "F10") (pinfunction "VDDQ_10_F10") (pintype "passive"))
      (node (ref "U1") (pin "F3") (pinfunction "VDDQ_9_F3") (pintype "passive"))
      (node (ref "U1") (pin "F5") (pinfunction "VDD2_3_F5") (pintype "passive"))
      (node (ref "U1") (pin "F8") (pinfunction "VDD2_4_F8") (pintype "passive"))
      (node (ref "U1") (pin "H1") (pinfunction "VDD2_5_H1") (pintype "passive"))
      (node (ref "U1") (pin "H12") (pinfunction "VDD2_8_H12") (pintype "passive"))
      (node (ref "U1") (pin "H5") (pinfunction "VDD2_6_H5") (pintype "passive"))
      (node (ref "U1") (pin "H8") (pinfunction "VDD2_7_H8") (pintype "passive"))
      (node (ref "U1") (pin "K1") (pinfunction "VDD2_9_K1") (pintype "passive"))
      (node (ref "U1") (pin "K10") (pinfunction "VDD2_11_K10") (pintype "passive"))
      (node (ref "U1") (pin "K12") (pinfunction "VDD2_12_K12") (pintype "passive"))
      (node (ref "U1") (pin "K3") (pinfunction "VDD2_10_K3") (pintype "passive"))
      (node (ref "U1") (pin "N1") (pinfunction "VDD2_13_N1") (pintype "passive"))
      (node (ref "U1") (pin "N10") (pinfunction "VDD2_15_N10") (pintype "passive"))
      (node (ref "U1") (pin "N12") (pinfunction "VDD2_16_N12") (pintype "passive"))
      (node (ref "U1") (pin "N3") (pinfunction "VDD2_14_N3") (pintype "passive"))
      (node (ref "U1") (pin "R1") (pinfunction "VDD2_17_R1") (pintype "passive"))
      (node (ref "U1") (pin "R12") (pinfunction "VDD2_20_R12") (pintype "passive"))
      (node (ref "U1") (pin "R5") (pinfunction "VDD2_18_R5") (pintype "passive"))
      (node (ref "U1") (pin "R8") (pinfunction "VDD2_19_R8") (pintype "passive"))
      (node (ref "U1") (pin "U10") (pinfunction "VDDQ_12_U10") (pintype "passive"))
      (node (ref "U1") (pin "U3") (pinfunction "VDDQ_11_U3") (pintype "passive"))
      (node (ref "U1") (pin "U5") (pinfunction "VDD2_21_U5") (pintype "passive"))
      (node (ref "U1") (pin "U8") (pinfunction "VDD2_22_U8") (pintype "passive"))
      (node (ref "U1") (pin "W1") (pinfunction "VDDQ_13_W1") (pintype "passive"))
      (node (ref "U1") (pin "W12") (pinfunction "VDDQ_16_W12") (pintype "passive"))
      (node (ref "U1") (pin "W5") (pinfunction "VDDQ_14_W5") (pintype "passive"))
      (node (ref "U1") (pin "W8") (pinfunction "VDDQ_15_W8") (pintype "passive"))
    )
    (net (code "93") (name "unconnected-(U1A-CKE2_A_NC-PadK8)") (class "Default")
      (node (ref "U1") (pin "K8") (pinfunction "CKE2_A_NC_K8") (pintype "passive+no_connect"))
    )
    (net (code "94") (name "unconnected-(U1A-CKE2_B_NC-PadN8)") (class "Default")
      (node (ref "U1") (pin "N8") (pinfunction "CKE2_B_NC_N8") (pintype "passive+no_connect"))
    )
    (net (code "95") (name "unconnected-(U1A-CS2_A_NC-PadK5)") (class "Default")
      (node (ref "U1") (pin "K5") (pinfunction "CS2_A_NC_K5") (pintype "passive+no_connect"))
    )
    (net (code "96") (name "unconnected-(U1A-CS2_B_NC-PadN5)") (class "Default")
      (node (ref "U1") (pin "N5") (pinfunction "CS2_B_NC_N5") (pintype "passive+no_connect"))
    )
    (net (code "97") (name "unconnected-(U1A-ZQ2_A_NC-PadG11)") (class "Default")
      (node (ref "U1") (pin "G11") (pinfunction "ZQ2_A_NC_G11") (pintype "passive+no_connect"))
    )
    (net (code "98") (name "unconnected-(U1B-DNU_1-PadA1)") (class "Default")
      (node (ref "U1") (pin "A1") (pinfunction "DNU_1_A1") (pintype "passive+no_connect"))
    )
    (net (code "99") (name "unconnected-(U1B-DNU_2-PadA2)") (class "Default")
      (node (ref "U1") (pin "A2") (pinfunction "DNU_2_A2") (pintype "passive+no_connect"))
    )
    (net (code "100") (name "unconnected-(U1B-DNU_3-PadA11)") (class "Default")
      (node (ref "U1") (pin "A11") (pinfunction "DNU_3_A11") (pintype "passive+no_connect"))
    )
    (net (code "101") (name "unconnected-(U1B-DNU_4-PadA12)") (class "Default")
      (node (ref "U1") (pin "A12") (pinfunction "DNU_4_A12") (pintype "passive+no_connect"))
    )
    (net (code "102") (name "unconnected-(U1B-DNU_5-PadB1)") (class "Default")
      (node (ref "U1") (pin "B1") (pinfunction "DNU_5_B1") (pintype "passive+no_connect"))
    )
    (net (code "103") (name "unconnected-(U1B-DNU_6-PadB12)") (class "Default")
      (node (ref "U1") (pin "B12") (pinfunction "DNU_6_B12") (pintype "passive+no_connect"))
    )
    (net (code "104") (name "unconnected-(U1B-DNU_7-PadAA1)") (class "Default")
      (node (ref "U1") (pin "AA1") (pinfunction "DNU_7_AA1") (pintype "passive+no_connect"))
    )
    (net (code "105") (name "unconnected-(U1B-DNU_8-PadAA12)") (class "Default")
      (node (ref "U1") (pin "AA12") (pinfunction "DNU_8_AA12") (pintype "passive+no_connect"))
    )
    (net (code "106") (name "unconnected-(U1B-DNU_9-PadAB1)") (class "Default")
      (node (ref "U1") (pin "AB1") (pinfunction "DNU_9_AB1") (pintype "passive+no_connect"))
    )
    (net (code "107") (name "unconnected-(U1B-DNU_10-PadAB2)") (class "Default")
      (node (ref "U1") (pin "AB2") (pinfunction "DNU_10_AB2") (pintype "passive+no_connect"))
    )
    (net (code "108") (name "unconnected-(U1B-DNU_11-PadAB11)") (class "Default")
      (node (ref "U1") (pin "AB11") (pinfunction "DNU_11_AB11") (pintype "passive+no_connect"))
    )
    (net (code "109") (name "unconnected-(U1B-DNU_12-PadAB12)") (class "Default")
      (node (ref "U1") (pin "AB12") (pinfunction "DNU_12_AB12") (pintype "passive+no_connect"))
    )
  )
)
